# Urukul.net
KiCad netlist of a schematic drawn in Altium Designer
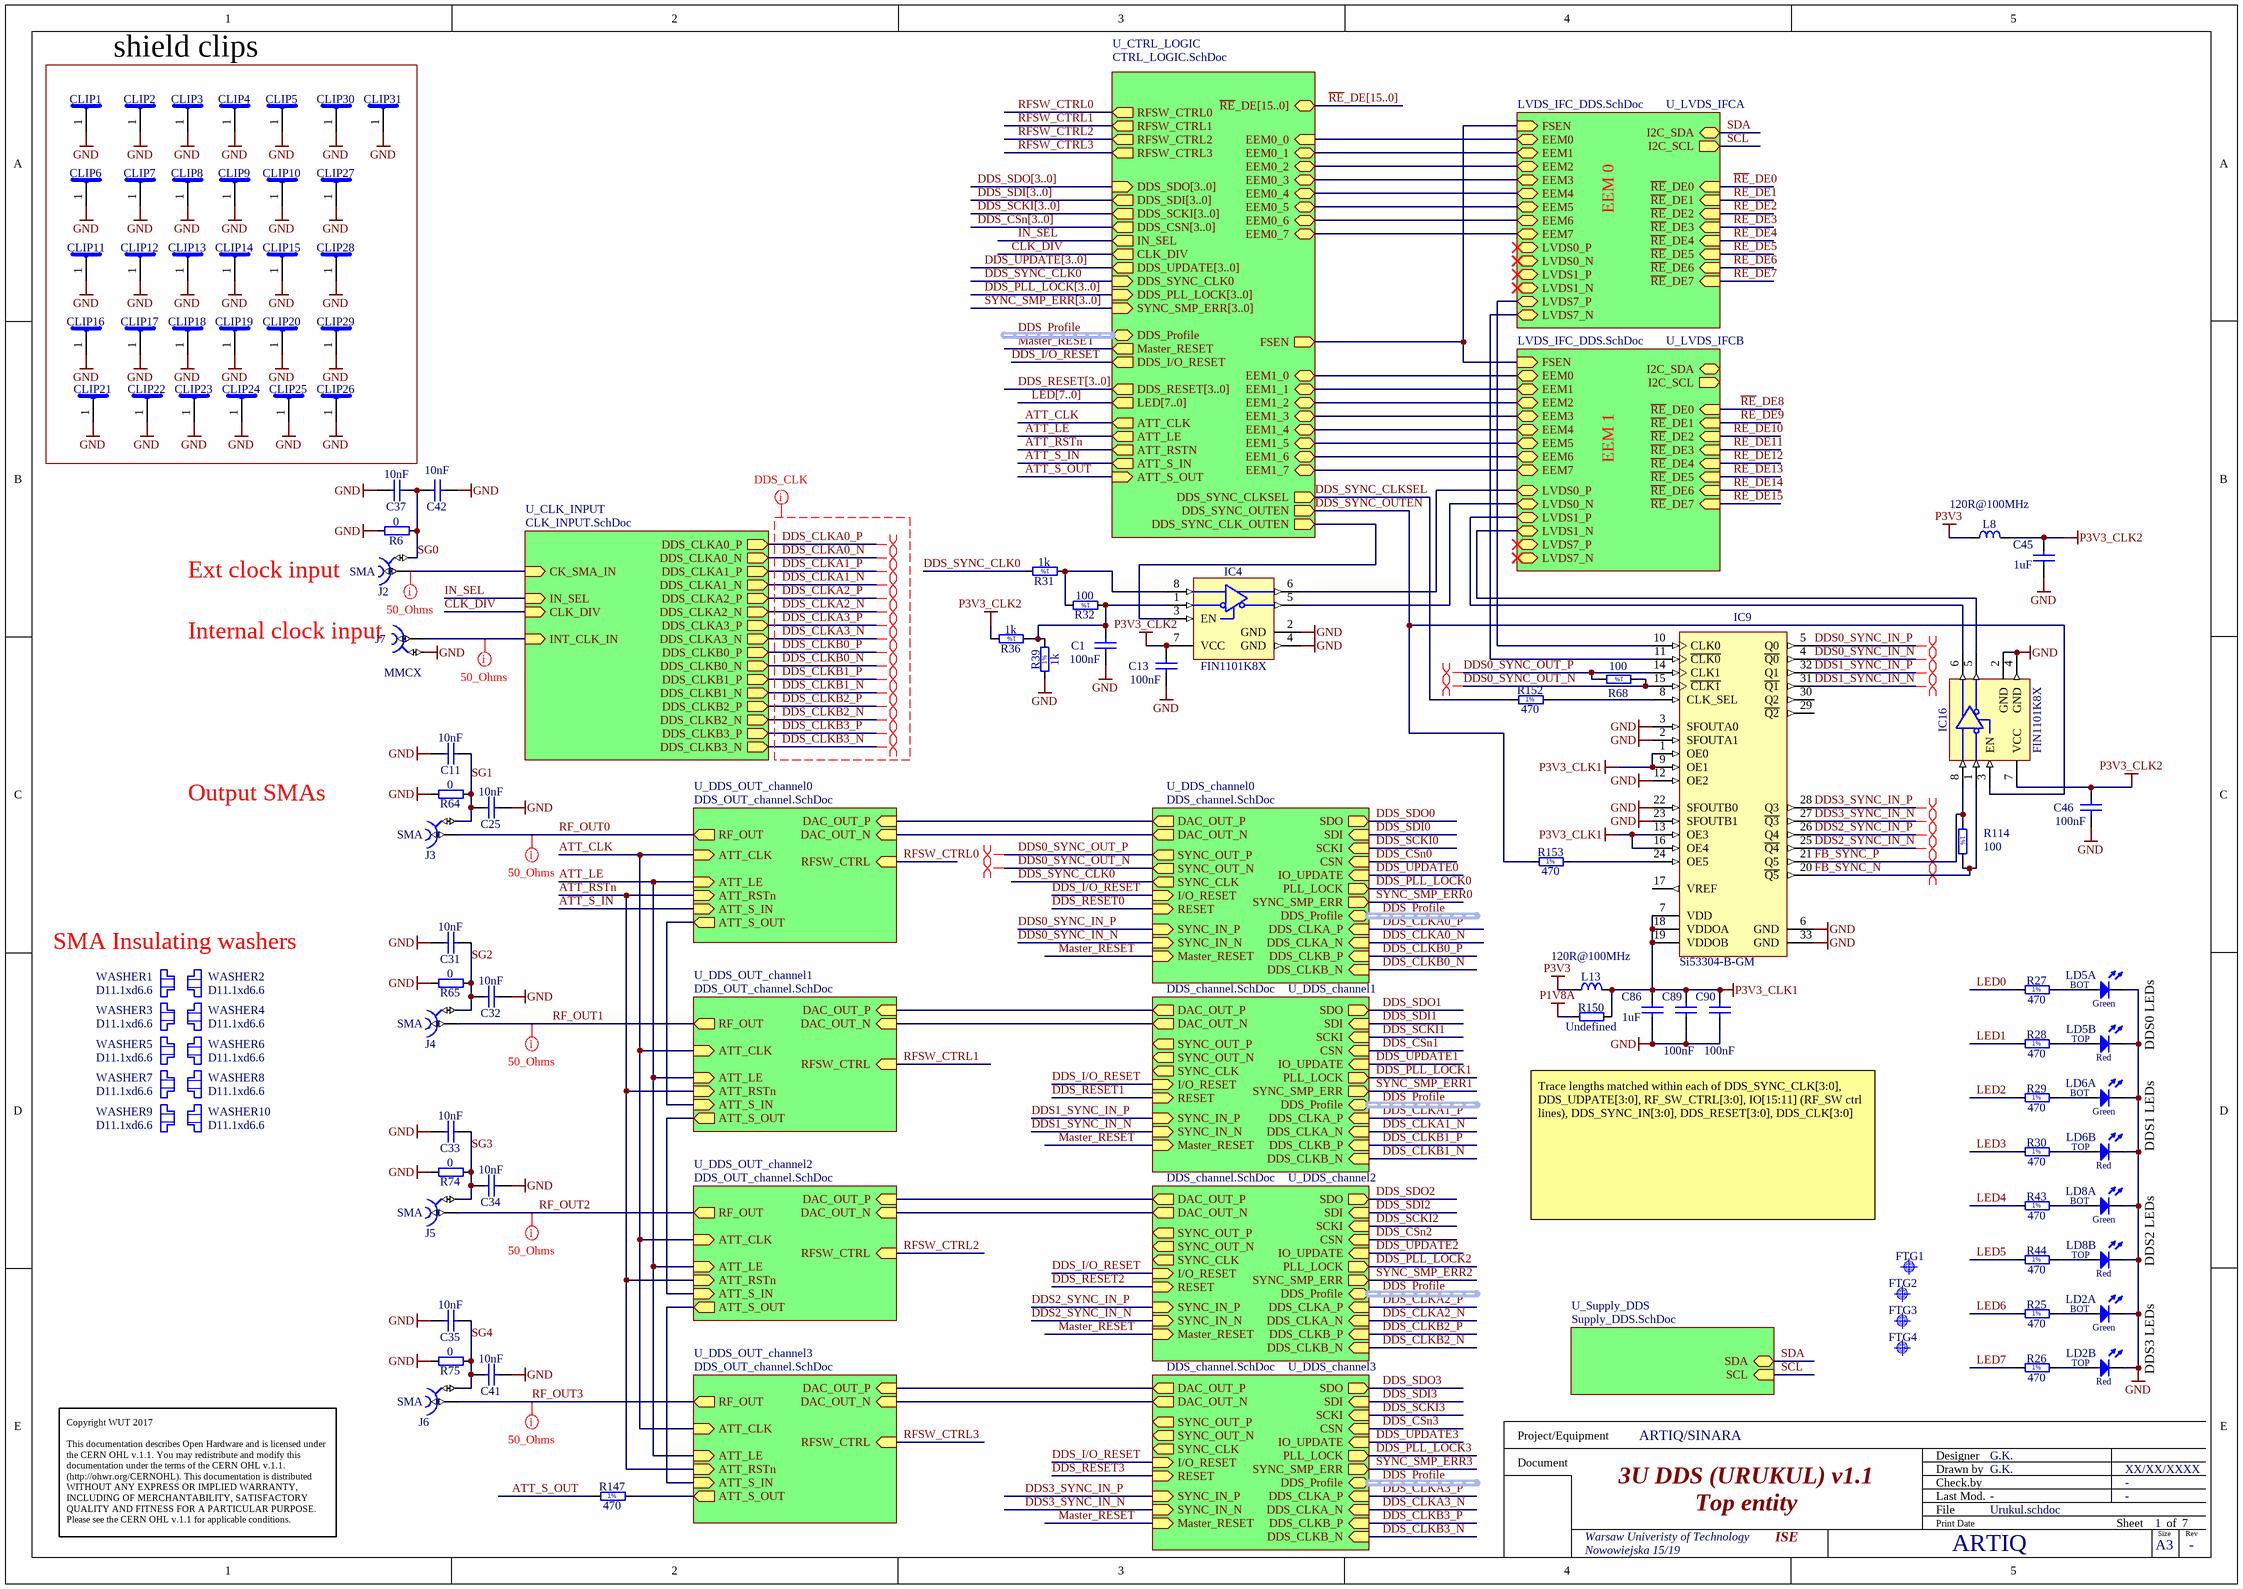
[diagram p0: Urukul.schdoc]

(export (version "E")
  (design (tool "Eeschema 10.0.6"))
  (components
    (comp (ref "C1")
      (value "100nF")
      (footprint "CAPC1005X55N")
      (description "Non-polarised capacitor")
      (fields
        (field (name "PART NUMBER") "CC0402_100NF_16V_10%_X5R")
        (field (name "VOLTAGE") "16V")
        (field (name "AUTHOR") "CERN DEM JLC")
      )
      (libsource (lib "Capacitors") (part "Capacitor - non polarized"))
    )
    (comp (ref "C11")
      (value "10nF")
      (footprint "CAPC1005X55N")
      (description "Non-polarised capacitor")
      (fields
        (field (name "PART NUMBER") "CC0402_10NF_16V_10%_X7R")
        (field (name "VOLTAGE") "16V")
        (field (name "AUTHOR") "CERN DEM JLC")
      )
      (libsource (lib "Capacitors") (part "Capacitor - non polarized"))
    )
    (comp (ref "C13")
      (value "100nF")
      (footprint "CAPC1005X55N")
      (description "Non-polarised capacitor")
      (fields
        (field (name "PART NUMBER") "CC0402_100NF_16V_10%_X5R")
        (field (name "VOLTAGE") "16V")
        (field (name "AUTHOR") "CERN DEM JLC")
      )
      (libsource (lib "Capacitors") (part "Capacitor - non polarized"))
    )
    (comp (ref "C25")
      (value "10nF")
      (footprint "CAPC1005X55N")
      (description "Non-polarised capacitor")
      (fields
        (field (name "PART NUMBER") "CC0402_10NF_16V_10%_X7R")
        (field (name "VOLTAGE") "16V")
        (field (name "AUTHOR") "CERN DEM JLC")
      )
      (libsource (lib "Capacitors") (part "Capacitor - non polarized"))
    )
    (comp (ref "C31")
      (value "10nF")
      (footprint "CAPC1005X55N")
      (description "Non-polarised capacitor")
      (fields
        (field (name "PART NUMBER") "CC0402_10NF_16V_10%_X7R")
        (field (name "VOLTAGE") "16V")
        (field (name "AUTHOR") "CERN DEM JLC")
      )
      (libsource (lib "Capacitors") (part "Capacitor - non polarized"))
    )
    (comp (ref "C32")
      (value "10nF")
      (footprint "CAPC1005X55N")
      (description "Non-polarised capacitor")
      (fields
        (field (name "PART NUMBER") "CC0402_10NF_16V_10%_X7R")
        (field (name "VOLTAGE") "16V")
        (field (name "AUTHOR") "CERN DEM JLC")
      )
      (libsource (lib "Capacitors") (part "Capacitor - non polarized"))
    )
    (comp (ref "C33")
      (value "10nF")
      (footprint "CAPC1005X55N")
      (description "Non-polarised capacitor")
      (fields
        (field (name "PART NUMBER") "CC0402_10NF_16V_10%_X7R")
        (field (name "VOLTAGE") "16V")
        (field (name "AUTHOR") "CERN DEM JLC")
      )
      (libsource (lib "Capacitors") (part "Capacitor - non polarized"))
    )
    (comp (ref "C34")
      (value "10nF")
      (footprint "CAPC1005X55N")
      (description "Non-polarised capacitor")
      (fields
        (field (name "PART NUMBER") "CC0402_10NF_16V_10%_X7R")
        (field (name "VOLTAGE") "16V")
        (field (name "AUTHOR") "CERN DEM JLC")
      )
      (libsource (lib "Capacitors") (part "Capacitor - non polarized"))
    )
    (comp (ref "C35")
      (value "10nF")
      (footprint "CAPC1005X55N")
      (description "Non-polarised capacitor")
      (fields
        (field (name "PART NUMBER") "CC0402_10NF_16V_10%_X7R")
        (field (name "VOLTAGE") "16V")
        (field (name "AUTHOR") "CERN DEM JLC")
      )
      (libsource (lib "Capacitors") (part "Capacitor - non polarized"))
    )
    (comp (ref "C37")
      (value "10nF")
      (footprint "CAPC1005X55N")
      (description "Non-polarised capacitor")
      (fields
        (field (name "PART NUMBER") "CC0402_10NF_16V_10%_X7R")
        (field (name "VOLTAGE") "16V")
        (field (name "AUTHOR") "CERN DEM JLC")
      )
      (libsource (lib "Capacitors") (part "Capacitor - non polarized"))
    )
    (comp (ref "C41")
      (value "10nF")
      (footprint "CAPC1005X55N")
      (description "Non-polarised capacitor")
      (fields
        (field (name "PART NUMBER") "CC0402_10NF_16V_10%_X7R")
        (field (name "VOLTAGE") "16V")
        (field (name "AUTHOR") "CERN DEM JLC")
      )
      (libsource (lib "Capacitors") (part "Capacitor - non polarized"))
    )
    (comp (ref "C42")
      (value "10nF")
      (footprint "CAPC1005X55N")
      (description "Non-polarised capacitor")
      (fields
        (field (name "PART NUMBER") "CC0402_10NF_16V_10%_X7R")
        (field (name "VOLTAGE") "16V")
        (field (name "AUTHOR") "CERN DEM JLC")
      )
      (libsource (lib "Capacitors") (part "Capacitor - non polarized"))
    )
    (comp (ref "C45")
      (value "1uF")
      (footprint "CAPC1005X55N")
      (description "Non-polarised capacitor")
      (fields
        (field (name "PART NUMBER") "CC0402_1UF_16V_10%_X5R")
        (field (name "VOLTAGE") "16V")
        (field (name "AUTHOR") "CERN DEM JLC")
      )
      (libsource (lib "Capacitors") (part "Capacitor - non polarized"))
    )
    (comp (ref "C46")
      (value "100nF")
      (footprint "CAPC1005X55N")
      (description "Non-polarised capacitor")
      (fields
        (field (name "PART NUMBER") "CC0402_100NF_16V_10%_X5R")
        (field (name "VOLTAGE") "16V")
        (field (name "AUTHOR") "CERN DEM JLC")
      )
      (libsource (lib "Capacitors") (part "Capacitor - non polarized"))
    )
    (comp (ref "C86")
      (value "1uF")
      (footprint "CAPC1005X55N")
      (description "Non-polarised capacitor")
      (fields
        (field (name "PART NUMBER") "CC0402_1UF_16V_10%_X5R")
        (field (name "VOLTAGE") "16V")
        (field (name "AUTHOR") "CERN DEM JLC")
      )
      (libsource (lib "Capacitors") (part "Capacitor - non polarized"))
    )
    (comp (ref "C89")
      (value "100nF")
      (footprint "CAPC1005X55N")
      (description "Non-polarised capacitor")
      (fields
        (field (name "PART NUMBER") "CC0402_100NF_16V_10%_X5R")
        (field (name "VOLTAGE") "16V")
        (field (name "AUTHOR") "CERN DEM JLC")
      )
      (libsource (lib "Capacitors") (part "Capacitor - non polarized"))
    )
    (comp (ref "C90")
      (value "100nF")
      (footprint "CAPC1005X55N")
      (description "Non-polarised capacitor")
      (fields
        (field (name "PART NUMBER") "CC0402_100NF_16V_10%_X5R")
        (field (name "VOLTAGE") "16V")
        (field (name "AUTHOR") "CERN DEM JLC")
      )
      (libsource (lib "Capacitors") (part "Capacitor - non polarized"))
    )
    (comp (ref "CLIP1")
      (value "S1411-46R")
      (footprint "CLIP_HOLLAND-SHIELDING_LC")
      (description "Surface Mount Clip for PCB Screening Covers")
      (fields (field (name "MANUFACTURER") "HARWIN") (field (name "AUTHOR") "CERN DEM JLC"))
      (libsource (lib "LIBRARY_SCH") (part "SHIELD_CLIP"))
    )
    (comp (ref "CLIP2")
      (value "S1411-46R")
      (footprint "CLIP_HOLLAND-SHIELDING_LC")
      (description "Surface Mount Clip for PCB Screening Covers")
      (fields (field (name "MANUFACTURER") "HARWIN") (field (name "AUTHOR") "CERN DEM JLC"))
      (libsource (lib "LIBRARY_SCH") (part "SHIELD_CLIP"))
    )
    (comp (ref "CLIP3")
      (value "S1411-46R")
      (footprint "CLIP_HOLLAND-SHIELDING_LC")
      (description "Surface Mount Clip for PCB Screening Covers")
      (fields (field (name "MANUFACTURER") "HARWIN") (field (name "AUTHOR") "CERN DEM JLC"))
      (libsource (lib "LIBRARY_SCH") (part "SHIELD_CLIP"))
    )
    (comp (ref "CLIP4")
      (value "S1411-46R")
      (footprint "CLIP_HOLLAND-SHIELDING_LC")
      (description "Surface Mount Clip for PCB Screening Covers")
      (fields (field (name "MANUFACTURER") "HARWIN") (field (name "AUTHOR") "CERN DEM JLC"))
      (libsource (lib "LIBRARY_SCH") (part "SHIELD_CLIP"))
    )
    (comp (ref "CLIP5")
      (value "S1411-46R")
      (footprint "CLIP_HOLLAND-SHIELDING_LC")
      (description "Surface Mount Clip for PCB Screening Covers")
      (fields (field (name "MANUFACTURER") "HARWIN") (field (name "AUTHOR") "CERN DEM JLC"))
      (libsource (lib "LIBRARY_SCH") (part "SHIELD_CLIP"))
    )
    (comp (ref "CLIP6")
      (value "S1411-46R")
      (footprint "CLIP_HOLLAND-SHIELDING_LC")
      (description "Surface Mount Clip for PCB Screening Covers")
      (fields (field (name "MANUFACTURER") "HARWIN") (field (name "AUTHOR") "CERN DEM JLC"))
      (libsource (lib "LIBRARY_SCH") (part "SHIELD_CLIP"))
    )
    (comp (ref "CLIP7")
      (value "S1411-46R")
      (footprint "CLIP_HOLLAND-SHIELDING_LC")
      (description "Surface Mount Clip for PCB Screening Covers")
      (fields (field (name "MANUFACTURER") "HARWIN") (field (name "AUTHOR") "CERN DEM JLC"))
      (libsource (lib "LIBRARY_SCH") (part "SHIELD_CLIP"))
    )
    (comp (ref "CLIP8")
      (value "S1411-46R")
      (footprint "CLIP_HOLLAND-SHIELDING_LC")
      (description "Surface Mount Clip for PCB Screening Covers")
      (fields (field (name "MANUFACTURER") "HARWIN") (field (name "AUTHOR") "CERN DEM JLC"))
      (libsource (lib "LIBRARY_SCH") (part "SHIELD_CLIP"))
    )
    (comp (ref "CLIP9")
      (value "S1411-46R")
      (footprint "CLIP_HOLLAND-SHIELDING_LC")
      (description "Surface Mount Clip for PCB Screening Covers")
      (fields (field (name "MANUFACTURER") "HARWIN") (field (name "AUTHOR") "CERN DEM JLC"))
      (libsource (lib "LIBRARY_SCH") (part "SHIELD_CLIP"))
    )
    (comp (ref "CLIP10")
      (value "S1411-46R")
      (footprint "CLIP_HOLLAND-SHIELDING_LC")
      (description "Surface Mount Clip for PCB Screening Covers")
      (fields (field (name "MANUFACTURER") "HARWIN") (field (name "AUTHOR") "CERN DEM JLC"))
      (libsource (lib "LIBRARY_SCH") (part "SHIELD_CLIP"))
    )
    (comp (ref "CLIP11")
      (value "S1411-46R")
      (footprint "CLIP_HOLLAND-SHIELDING_LC")
      (description "Surface Mount Clip for PCB Screening Covers")
      (fields (field (name "MANUFACTURER") "HARWIN") (field (name "AUTHOR") "CERN DEM JLC"))
      (libsource (lib "LIBRARY_SCH") (part "SHIELD_CLIP"))
    )
    (comp (ref "CLIP12")
      (value "S1411-46R")
      (footprint "CLIP_HOLLAND-SHIELDING_LC")
      (description "Surface Mount Clip for PCB Screening Covers")
      (fields (field (name "MANUFACTURER") "HARWIN") (field (name "AUTHOR") "CERN DEM JLC"))
      (libsource (lib "LIBRARY_SCH") (part "SHIELD_CLIP"))
    )
    (comp (ref "CLIP13")
      (value "S1411-46R")
      (footprint "CLIP_HOLLAND-SHIELDING_LC")
      (description "Surface Mount Clip for PCB Screening Covers")
      (fields (field (name "MANUFACTURER") "HARWIN") (field (name "AUTHOR") "CERN DEM JLC"))
      (libsource (lib "LIBRARY_SCH") (part "SHIELD_CLIP"))
    )
    (comp (ref "CLIP14")
      (value "S1411-46R")
      (footprint "CLIP_HOLLAND-SHIELDING_LC")
      (description "Surface Mount Clip for PCB Screening Covers")
      (fields (field (name "MANUFACTURER") "HARWIN") (field (name "AUTHOR") "CERN DEM JLC"))
      (libsource (lib "LIBRARY_SCH") (part "SHIELD_CLIP"))
    )
    (comp (ref "CLIP15")
      (value "S1411-46R")
      (footprint "CLIP_HOLLAND-SHIELDING_LC")
      (description "Surface Mount Clip for PCB Screening Covers")
      (fields (field (name "MANUFACTURER") "HARWIN") (field (name "AUTHOR") "CERN DEM JLC"))
      (libsource (lib "LIBRARY_SCH") (part "SHIELD_CLIP"))
    )
    (comp (ref "CLIP16")
      (value "S1411-46R")
      (footprint "CLIP_HOLLAND-SHIELDING_LC")
      (description "Surface Mount Clip for PCB Screening Covers")
      (fields (field (name "MANUFACTURER") "HARWIN") (field (name "AUTHOR") "CERN DEM JLC"))
      (libsource (lib "LIBRARY_SCH") (part "SHIELD_CLIP"))
    )
    (comp (ref "CLIP17")
      (value "S1411-46R")
      (footprint "CLIP_HOLLAND-SHIELDING_LC")
      (description "Surface Mount Clip for PCB Screening Covers")
      (fields (field (name "MANUFACTURER") "HARWIN") (field (name "AUTHOR") "CERN DEM JLC"))
      (libsource (lib "LIBRARY_SCH") (part "SHIELD_CLIP"))
    )
    (comp (ref "CLIP18")
      (value "S1411-46R")
      (footprint "CLIP_HOLLAND-SHIELDING_LC")
      (description "Surface Mount Clip for PCB Screening Covers")
      (fields (field (name "MANUFACTURER") "HARWIN") (field (name "AUTHOR") "CERN DEM JLC"))
      (libsource (lib "LIBRARY_SCH") (part "SHIELD_CLIP"))
    )
    (comp (ref "CLIP19")
      (value "S1411-46R")
      (footprint "CLIP_HOLLAND-SHIELDING_LC")
      (description "Surface Mount Clip for PCB Screening Covers")
      (fields (field (name "MANUFACTURER") "HARWIN") (field (name "AUTHOR") "CERN DEM JLC"))
      (libsource (lib "LIBRARY_SCH") (part "SHIELD_CLIP"))
    )
    (comp (ref "CLIP20")
      (value "S1411-46R")
      (footprint "CLIP_HOLLAND-SHIELDING_LC")
      (description "Surface Mount Clip for PCB Screening Covers")
      (fields (field (name "MANUFACTURER") "HARWIN") (field (name "AUTHOR") "CERN DEM JLC"))
      (libsource (lib "LIBRARY_SCH") (part "SHIELD_CLIP"))
    )
    (comp (ref "CLIP21")
      (value "S1411-46R")
      (footprint "CLIP_HOLLAND-SHIELDING_LC")
      (description "Surface Mount Clip for PCB Screening Covers")
      (fields (field (name "MANUFACTURER") "HARWIN") (field (name "AUTHOR") "CERN DEM JLC"))
      (libsource (lib "LIBRARY_SCH") (part "SHIELD_CLIP"))
    )
    (comp (ref "CLIP22")
      (value "S1411-46R")
      (footprint "CLIP_HOLLAND-SHIELDING_LC")
      (description "Surface Mount Clip for PCB Screening Covers")
      (fields (field (name "MANUFACTURER") "HARWIN") (field (name "AUTHOR") "CERN DEM JLC"))
      (libsource (lib "LIBRARY_SCH") (part "SHIELD_CLIP"))
    )
    (comp (ref "CLIP23")
      (value "S1411-46R")
      (footprint "CLIP_HOLLAND-SHIELDING_LC")
      (description "Surface Mount Clip for PCB Screening Covers")
      (fields (field (name "MANUFACTURER") "HARWIN") (field (name "AUTHOR") "CERN DEM JLC"))
      (libsource (lib "LIBRARY_SCH") (part "SHIELD_CLIP"))
    )
    (comp (ref "CLIP24")
      (value "S1411-46R")
      (footprint "CLIP_HOLLAND-SHIELDING_LC")
      (description "Surface Mount Clip for PCB Screening Covers")
      (fields (field (name "MANUFACTURER") "HARWIN") (field (name "AUTHOR") "CERN DEM JLC"))
      (libsource (lib "LIBRARY_SCH") (part "SHIELD_CLIP"))
    )
    (comp (ref "CLIP25")
      (value "S1411-46R")
      (footprint "CLIP_HOLLAND-SHIELDING_LC")
      (description "Surface Mount Clip for PCB Screening Covers")
      (fields (field (name "MANUFACTURER") "HARWIN") (field (name "AUTHOR") "CERN DEM JLC"))
      (libsource (lib "LIBRARY_SCH") (part "SHIELD_CLIP"))
    )
    (comp (ref "CLIP26")
      (value "S1411-46R")
      (footprint "CLIP_HOLLAND-SHIELDING_LC")
      (description "Surface Mount Clip for PCB Screening Covers")
      (fields (field (name "MANUFACTURER") "HARWIN") (field (name "AUTHOR") "CERN DEM JLC"))
      (libsource (lib "LIBRARY_SCH") (part "SHIELD_CLIP"))
    )
    (comp (ref "CLIP27")
      (value "S1411-46R")
      (footprint "CLIP_HOLLAND-SHIELDING_LC")
      (description "Surface Mount Clip for PCB Screening Covers")
      (fields (field (name "MANUFACTURER") "HARWIN") (field (name "AUTHOR") "CERN DEM JLC"))
      (libsource (lib "LIBRARY_SCH") (part "SHIELD_CLIP"))
    )
    (comp (ref "CLIP28")
      (value "S1411-46R")
      (footprint "CLIP_HOLLAND-SHIELDING_LC")
      (description "Surface Mount Clip for PCB Screening Covers")
      (fields (field (name "MANUFACTURER") "HARWIN") (field (name "AUTHOR") "CERN DEM JLC"))
      (libsource (lib "LIBRARY_SCH") (part "SHIELD_CLIP"))
    )
    (comp (ref "CLIP29")
      (value "S1411-46R")
      (footprint "CLIP_HOLLAND-SHIELDING_LC")
      (description "Surface Mount Clip for PCB Screening Covers")
      (fields (field (name "MANUFACTURER") "HARWIN") (field (name "AUTHOR") "CERN DEM JLC"))
      (libsource (lib "LIBRARY_SCH") (part "SHIELD_CLIP"))
    )
    (comp (ref "CLIP30")
      (value "S1411-46R")
      (footprint "CLIP_HOLLAND-SHIELDING_LC")
      (description "Surface Mount Clip for PCB Screening Covers")
      (fields (field (name "MANUFACTURER") "HARWIN") (field (name "AUTHOR") "CERN DEM JLC"))
      (libsource (lib "LIBRARY_SCH") (part "SHIELD_CLIP"))
    )
    (comp (ref "CLIP31")
      (value "S1411-46R")
      (footprint "CLIP_HOLLAND-SHIELDING_LC")
      (description "Surface Mount Clip for PCB Screening Covers")
      (fields (field (name "MANUFACTURER") "HARWIN") (field (name "AUTHOR") "CERN DEM JLC"))
      (libsource (lib "LIBRARY_SCH") (part "SHIELD_CLIP"))
    )
    (comp (ref "FTG1")
      (value "Use only in PCB")
      (footprint "FIDUCIAL_TOP_C100-200")
      (description "Fiducial Target")
      (fields (field (name "PART NUMBER") "FIDUCIAL_TARGET_C100-200") (field (name "AUTHOR") "CERN DEM JLC"))
      (libsource (lib "Eletro-mechanical") (part "Fiducial Target"))
    )
    (comp (ref "FTG2")
      (value "Use only in PCB")
      (footprint "FIDUCIAL_TOP_S100-200")
      (description "Fiducial Target")
      (fields (field (name "PART NUMBER") "FIDUCIAL_TARGET_S100-200") (field (name "AUTHOR") "CERN DEM JLC"))
      (libsource (lib "Eletro-mechanical") (part "Fiducial Target"))
    )
    (comp (ref "FTG3")
      (value "Use only in PCB")
      (footprint "FIDUCIAL_TOP_S200-400")
      (description "Fiducial Target")
      (fields (field (name "PART NUMBER") "FIDUCIAL_TARGET_S200-400") (field (name "AUTHOR") "CERN DEM JLC"))
      (libsource (lib "Eletro-mechanical") (part "Fiducial Target"))
    )
    (comp (ref "FTG4")
      (value "Use only in PCB")
      (footprint "FIDUCIAL_TOP_S100-200")
      (description "Fiducial Target")
      (fields (field (name "PART NUMBER") "FIDUCIAL_TARGET_S100-200") (field (name "AUTHOR") "CERN DEM JLC"))
      (libsource (lib "Eletro-mechanical") (part "Fiducial Target"))
    )
    (comp (ref "IC4")
      (value "FIN1101K8X")
      (footprint "SOP50P310X90-8N")
      (description "LVDS Single Port High Speed Repeater")
      (fields (field (name "MANUFACTURER") "FAIRCHILD SEMICONDUCTOR") (field (name "AUTHOR") "CERN DEM JLC"))
      (libsource (lib "") (part "FIN1101K8X_1"))
    )
    (comp (ref "IC9")
      (value "Si53304-B-GM")
      (footprint "SLAB-QFN-32-2150x2150TP_M")
      (fields (field (name "MANUFACTURER") "Silicon Labs"))
      (libsource (lib "Altium Content Vault") (part "SLAB-Si533X4-QFN-32-33"))
    )
    (comp (ref "IC16")
      (value "FIN1101K8X")
      (footprint "SOP50P310X90-8N")
      (description "LVDS Single Port High Speed Repeater")
      (fields (field (name "MANUFACTURER") "FAIRCHILD SEMICONDUCTOR") (field (name "AUTHOR") "CERN DEM JLC"))
      (libsource (lib "ICs And Semiconductors") (part "FIN1101K8X"))
    )
    (comp (ref "J2")
      (value "SMA")
      (footprint "RF249BT0050GHDW")
      (description "50 Ohm Through Hole SMA Right Angle PCB Jack")
      (fields
        (field (name "PART NUMBER") "AdamTech_RF249BT0050GHDW")
        (field (name "MANUFACTURER") "AdamTech")
        (field (name "AUTHOR") "GK")
      )
      (libsource (lib "LIBRARY_SCH") (part "CON_SMA_RF249BT0050GHDW"))
    )
    (comp (ref "J3")
      (value "SMA")
      (footprint "RF249BT0050GHDW")
      (description "50 Ohm Through Hole SMA Right Angle PCB Jack")
      (fields
        (field (name "PART NUMBER") "AdamTech_RF249BT0050GHDW")
        (field (name "MANUFACTURER") "AdamTech")
        (field (name "AUTHOR") "GK")
      )
      (libsource (lib "LIBRARY_SCH") (part "CON_SMA_RF249BT0050GHDW"))
    )
    (comp (ref "J4")
      (value "SMA")
      (footprint "RF249BT0050GHDW")
      (description "50 Ohm Through Hole SMA Right Angle PCB Jack")
      (fields
        (field (name "PART NUMBER") "AdamTech_RF249BT0050GHDW")
        (field (name "MANUFACTURER") "AdamTech")
        (field (name "AUTHOR") "GK")
      )
      (libsource (lib "LIBRARY_SCH") (part "CON_SMA_RF249BT0050GHDW"))
    )
    (comp (ref "J5")
      (value "SMA")
      (footprint "RF249BT0050GHDW")
      (description "50 Ohm Through Hole SMA Right Angle PCB Jack")
      (fields
        (field (name "PART NUMBER") "AdamTech_RF249BT0050GHDW")
        (field (name "MANUFACTURER") "AdamTech")
        (field (name "AUTHOR") "GK")
      )
      (libsource (lib "LIBRARY_SCH") (part "CON_SMA_RF249BT0050GHDW"))
    )
    (comp (ref "J6")
      (value "SMA")
      (footprint "RF249BT0050GHDW")
      (description "50 Ohm Through Hole SMA Right Angle PCB Jack")
      (fields
        (field (name "PART NUMBER") "AdamTech_RF249BT0050GHDW")
        (field (name "MANUFACTURER") "AdamTech")
        (field (name "AUTHOR") "GK")
      )
      (libsource (lib "LIBRARY_SCH") (part "CON_SMA_RF249BT0050GHDW"))
    )
    (comp (ref "J7")
      (value "MMCX")
      (footprint "SAMTEC_MMCX-J-P-H-ST-TH1")
      (fields
        (field (name "PART NUMBER") "SAMTEC_MMCX-J-P-H-ST-TH1")
        (field (name "MANUFACTURER") "SAMTEC")
        (field (name "MANUFACTURER PART NUMBER") "MMCX-J-P-H-ST-TH1")
        (field (name "AUTHOR") "CERN DEM JLC")
      )
      (libsource (lib "Connectors") (part "Coax_1Female_1Shield"))
    )
    (comp (ref "L8")
      (value "120R@100MHz")
      (footprint "INDC1608X95N")
      (description "Inductor")
      (fields
        (field (name "PART NUMBER") "IND0603_MURATA_BLM18PG121SN1D")
        (field (name "POWER") "2A")
        (field (name "AUTHOR") "CERN DEM BC")
      )
      (libsource (lib "Inductors & Transformers") (part "Inductor"))
    )
    (comp (ref "L13")
      (value "120R@100MHz")
      (footprint "INDC1608X95N")
      (description "Inductor")
      (fields
        (field (name "PART NUMBER") "IND0603_MURATA_BLM18PG121SN1D")
        (field (name "POWER") "2A")
        (field (name "AUTHOR") "CERN DEM BC")
      )
      (libsource (lib "Inductors & Transformers") (part "Inductor"))
    )
    (comp (ref "LD2")
      (value "Red/Green")
      (footprint "LED_DIALIGHT_553-0112-200F")
      (description "2x LED  Botom Green, Top Red")
      (fields
        (field (name "PART NUMBER") "LED_DIALIGHT_553-0112-200F")
        (field (name "MANUFACTURER") "DIALIGHT")
        (field (name "AUTHOR") "CERN DEM JMW")
      )
      (libsource (lib "ICs And Semiconductors") (part "LED x2 G-1C2A-BOT_R-3C4A-TOP"))
    )
    (comp (ref "LD5")
      (value "Red/Green")
      (footprint "LED_DIALIGHT_553-0112-200F")
      (description "2x LED  Botom Green, Top Red")
      (fields
        (field (name "PART NUMBER") "LED_DIALIGHT_553-0112-200F")
        (field (name "MANUFACTURER") "DIALIGHT")
        (field (name "AUTHOR") "CERN DEM JMW")
      )
      (libsource (lib "ICs And Semiconductors") (part "LED x2 G-1C2A-BOT_R-3C4A-TOP"))
    )
    (comp (ref "LD6")
      (value "Red/Green")
      (footprint "LED_DIALIGHT_553-0112-200F")
      (description "2x LED  Botom Green, Top Red")
      (fields
        (field (name "PART NUMBER") "LED_DIALIGHT_553-0112-200F")
        (field (name "MANUFACTURER") "DIALIGHT")
        (field (name "AUTHOR") "CERN DEM JMW")
      )
      (libsource (lib "ICs And Semiconductors") (part "LED x2 G-1C2A-BOT_R-3C4A-TOP"))
    )
    (comp (ref "LD8")
      (value "Red/Green")
      (footprint "LED_DIALIGHT_553-0112-200F")
      (description "2x LED  Botom Green, Top Red")
      (fields
        (field (name "PART NUMBER") "LED_DIALIGHT_553-0112-200F")
        (field (name "MANUFACTURER") "DIALIGHT")
        (field (name "AUTHOR") "CERN DEM JMW")
      )
      (libsource (lib "ICs And Semiconductors") (part "LED x2 G-1C2A-BOT_R-3C4A-TOP"))
    )
    (comp (ref "R6")
      (value "0")
      (footprint "RESC1005X40N")
      (description "Resistor")
      (fields
        (field (name "PART NUMBER") "R0402_0R_JUMPER")
        (field (name "MANUFACTURER") "GENERIC")
        (field (name "AUTHOR") "CERN DEM JLC")
      )
      (libsource (lib "Resistors") (part "Resistor"))
    )
    (comp (ref "R25")
      (value "470")
      (footprint "RESC1005X40N")
      (description "Resistor - 1%")
      (fields
        (field (name "PART NUMBER") "R0402_470R_1%_0.0625W_100PPM")
        (field (name "POWER") "0.0625W")
        (field (name "AUTHOR") "CERN DEM JLC")
      )
      (libsource (lib "Resistors") (part "Resistor - 1%"))
    )
    (comp (ref "R26")
      (value "470")
      (footprint "RESC1005X40N")
      (description "Resistor - 1%")
      (fields
        (field (name "PART NUMBER") "R0402_470R_1%_0.0625W_100PPM")
        (field (name "POWER") "0.0625W")
        (field (name "AUTHOR") "CERN DEM JLC")
      )
      (libsource (lib "Resistors") (part "Resistor - 1%"))
    )
    (comp (ref "R27")
      (value "470")
      (footprint "RESC1005X40N")
      (description "Resistor - 1%")
      (fields
        (field (name "PART NUMBER") "R0402_470R_1%_0.0625W_100PPM")
        (field (name "POWER") "0.0625W")
        (field (name "AUTHOR") "CERN DEM JLC")
      )
      (libsource (lib "Resistors") (part "Resistor - 1%"))
    )
    (comp (ref "R28")
      (value "470")
      (footprint "RESC1005X40N")
      (description "Resistor - 1%")
      (fields
        (field (name "PART NUMBER") "R0402_470R_1%_0.0625W_100PPM")
        (field (name "POWER") "0.0625W")
        (field (name "AUTHOR") "CERN DEM JLC")
      )
      (libsource (lib "Resistors") (part "Resistor - 1%"))
    )
    (comp (ref "R29")
      (value "470")
      (footprint "RESC1005X40N")
      (description "Resistor - 1%")
      (fields
        (field (name "PART NUMBER") "R0402_470R_1%_0.0625W_100PPM")
        (field (name "POWER") "0.0625W")
        (field (name "AUTHOR") "CERN DEM JLC")
      )
      (libsource (lib "Resistors") (part "Resistor - 1%"))
    )
    (comp (ref "R30")
      (value "470")
      (footprint "RESC1005X40N")
      (description "Resistor - 1%")
      (fields
        (field (name "PART NUMBER") "R0402_470R_1%_0.0625W_100PPM")
        (field (name "POWER") "0.0625W")
        (field (name "AUTHOR") "CERN DEM JLC")
      )
      (libsource (lib "Resistors") (part "Resistor - 1%"))
    )
    (comp (ref "R31")
      (value "1k")
      (footprint "RESC1005X40N")
      (description "Resistor - 1%")
      (fields
        (field (name "PART NUMBER") "R0402_1K_1%_0.0625W_100PPM")
        (field (name "POWER") "0.0625W")
        (field (name "AUTHOR") "CERN DEM JLC")
      )
      (libsource (lib "Resistors") (part "Resistor - 1%"))
    )
    (comp (ref "R32")
      (value "100")
      (footprint "RESC1005X40N")
      (description "Resistor - 1%")
      (fields
        (field (name "PART NUMBER") "R0402_100R_1%_0.0625W_100PPM")
        (field (name "POWER") "0.0625W")
        (field (name "AUTHOR") "CERN DEM JLC")
      )
      (libsource (lib "Resistors") (part "Resistor - 1%"))
    )
    (comp (ref "R36")
      (value "1k")
      (footprint "RESC1005X40N")
      (description "Resistor - 1%")
      (fields
        (field (name "PART NUMBER") "R0402_1K_1%_0.0625W_100PPM")
        (field (name "POWER") "0.0625W")
        (field (name "AUTHOR") "CERN DEM JLC")
      )
      (libsource (lib "Resistors") (part "Resistor - 1%"))
    )
    (comp (ref "R39")
      (value "1k")
      (footprint "RESC1005X40N")
      (description "Resistor - 1%")
      (fields
        (field (name "PART NUMBER") "R0402_1K_1%_0.0625W_100PPM")
        (field (name "POWER") "0.0625W")
        (field (name "AUTHOR") "CERN DEM JLC")
      )
      (libsource (lib "Resistors") (part "Resistor - 1%"))
    )
    (comp (ref "R43")
      (value "470")
      (footprint "RESC1005X40N")
      (description "Resistor - 1%")
      (fields
        (field (name "PART NUMBER") "R0402_470R_1%_0.0625W_100PPM")
        (field (name "POWER") "0.0625W")
        (field (name "AUTHOR") "CERN DEM JLC")
      )
      (libsource (lib "Resistors") (part "Resistor - 1%"))
    )
    (comp (ref "R44")
      (value "470")
      (footprint "RESC1005X40N")
      (description "Resistor - 1%")
      (fields
        (field (name "PART NUMBER") "R0402_470R_1%_0.0625W_100PPM")
        (field (name "POWER") "0.0625W")
        (field (name "AUTHOR") "CERN DEM JLC")
      )
      (libsource (lib "Resistors") (part "Resistor - 1%"))
    )
    (comp (ref "R64")
      (value "0")
      (footprint "RESC1005X40N")
      (description "Resistor")
      (fields
        (field (name "PART NUMBER") "R0402_0R_JUMPER")
        (field (name "MANUFACTURER") "GENERIC")
        (field (name "AUTHOR") "CERN DEM JLC")
      )
      (libsource (lib "Resistors") (part "Resistor"))
    )
    (comp (ref "R65")
      (value "0")
      (footprint "RESC1005X40N")
      (description "Resistor")
      (fields
        (field (name "PART NUMBER") "R0402_0R_JUMPER")
        (field (name "MANUFACTURER") "GENERIC")
        (field (name "AUTHOR") "CERN DEM JLC")
      )
      (libsource (lib "Resistors") (part "Resistor"))
    )
    (comp (ref "R68")
      (value "100")
      (footprint "RESC1005X40N")
      (description "Resistor - 1%")
      (fields
        (field (name "PART NUMBER") "R0402_100R_1%_0.0625W_100PPM")
        (field (name "POWER") "0.0625W")
        (field (name "AUTHOR") "CERN DEM JLC")
      )
      (libsource (lib "Resistors") (part "Resistor - 1%"))
    )
    (comp (ref "R74")
      (value "0")
      (footprint "RESC1005X40N")
      (description "Resistor")
      (fields
        (field (name "PART NUMBER") "R0402_0R_JUMPER")
        (field (name "MANUFACTURER") "GENERIC")
        (field (name "AUTHOR") "CERN DEM JLC")
      )
      (libsource (lib "Resistors") (part "Resistor"))
    )
    (comp (ref "R75")
      (value "0")
      (footprint "RESC1005X40N")
      (description "Resistor")
      (fields
        (field (name "PART NUMBER") "R0402_0R_JUMPER")
        (field (name "MANUFACTURER") "GENERIC")
        (field (name "AUTHOR") "CERN DEM JLC")
      )
      (libsource (lib "Resistors") (part "Resistor"))
    )
    (comp (ref "R114")
      (value "100")
      (footprint "RESC1005X40N")
      (description "Resistor - 1%")
      (fields
        (field (name "PART NUMBER") "R0402_100R_1%_0.0625W_100PPM")
        (field (name "POWER") "0.0625W")
        (field (name "AUTHOR") "CERN DEM JLC")
      )
      (libsource (lib "Resistors") (part "Resistor - 1%"))
    )
    (comp (ref "R147")
      (value "470")
      (footprint "RESC1005X40N")
      (description "Resistor - 1%")
      (fields
        (field (name "PART NUMBER") "R0402_470R_1%_0.0625W_100PPM")
        (field (name "POWER") "0.0625W")
        (field (name "AUTHOR") "CERN DEM JLC")
      )
      (libsource (lib "Resistors") (part "Resistor - 1%"))
    )
    (comp (ref "R150")
      (value "Undefined")
      (footprint "RESC1608X55N")
      (description "Resistor")
      (fields (field (name "PART NUMBER") "R0603_NO-VALUE") (field (name "AUTHOR") "CERN DEM JLC"))
      (libsource (lib "Resistors") (part "Resistor"))
    )
    (comp (ref "R152")
      (value "470")
      (footprint "RESC1005X40N")
      (description "Resistor - 1%")
      (fields
        (field (name "PART NUMBER") "R0402_470R_1%_0.0625W_100PPM")
        (field (name "POWER") "0.0625W")
        (field (name "AUTHOR") "CERN DEM JLC")
      )
      (libsource (lib "Resistors") (part "Resistor - 1%"))
    )
    (comp (ref "R153")
      (value "470")
      (footprint "RESC1005X40N")
      (description "Resistor - 1%")
      (fields
        (field (name "PART NUMBER") "R0402_470R_1%_0.0625W_100PPM")
        (field (name "POWER") "0.0625W")
        (field (name "AUTHOR") "CERN DEM JLC")
      )
      (libsource (lib "Resistors") (part "Resistor - 1%"))
    )
    (comp (ref "WASHER1")
      (value "D11.1xd6.6")
      (footprint "Keystone_7687")
      (description "SMA_Shoulder Washer")
      (fields
        (field (name "PART NUMBER") "Keystone 7687")
        (field (name "MANUFACTURER") "Keystone")
        (field (name "AUTHOR") "GK")
      )
      (libsource (lib "LIBRARY_SCH") (part "Keystone_7687"))
    )
    (comp (ref "WASHER2")
      (value "D11.1xd6.6")
      (footprint "Keystone_7687")
      (description "SMA_Shoulder Washer")
      (fields
        (field (name "PART NUMBER") "Keystone 7687")
        (field (name "MANUFACTURER") "Keystone")
        (field (name "AUTHOR") "GK")
      )
      (libsource (lib "LIBRARY_SCH") (part "Keystone_7687"))
    )
    (comp (ref "WASHER3")
      (value "D11.1xd6.6")
      (footprint "Keystone_7687")
      (description "SMA_Shoulder Washer")
      (fields
        (field (name "PART NUMBER") "Keystone 7687")
        (field (name "MANUFACTURER") "Keystone")
        (field (name "AUTHOR") "GK")
      )
      (libsource (lib "LIBRARY_SCH") (part "Keystone_7687"))
    )
    (comp (ref "WASHER4")
      (value "D11.1xd6.6")
      (footprint "Keystone_7687")
      (description "SMA_Shoulder Washer")
      (fields
        (field (name "PART NUMBER") "Keystone 7687")
        (field (name "MANUFACTURER") "Keystone")
        (field (name "AUTHOR") "GK")
      )
      (libsource (lib "LIBRARY_SCH") (part "Keystone_7687"))
    )
    (comp (ref "WASHER5")
      (value "D11.1xd6.6")
      (footprint "Keystone_7687")
      (description "SMA_Shoulder Washer")
      (fields
        (field (name "PART NUMBER") "Keystone 7687")
        (field (name "MANUFACTURER") "Keystone")
        (field (name "AUTHOR") "GK")
      )
      (libsource (lib "LIBRARY_SCH") (part "Keystone_7687"))
    )
    (comp (ref "WASHER6")
      (value "D11.1xd6.6")
      (footprint "Keystone_7687")
      (description "SMA_Shoulder Washer")
      (fields
        (field (name "PART NUMBER") "Keystone 7687")
        (field (name "MANUFACTURER") "Keystone")
        (field (name "AUTHOR") "GK")
      )
      (libsource (lib "LIBRARY_SCH") (part "Keystone_7687"))
    )
    (comp (ref "WASHER7")
      (value "D11.1xd6.6")
      (footprint "Keystone_7687")
      (description "SMA_Shoulder Washer")
      (fields
        (field (name "PART NUMBER") "Keystone 7687")
        (field (name "MANUFACTURER") "Keystone")
        (field (name "AUTHOR") "GK")
      )
      (libsource (lib "LIBRARY_SCH") (part "Keystone_7687"))
    )
    (comp (ref "WASHER8")
      (value "D11.1xd6.6")
      (footprint "Keystone_7687")
      (description "SMA_Shoulder Washer")
      (fields
        (field (name "PART NUMBER") "Keystone 7687")
        (field (name "MANUFACTURER") "Keystone")
        (field (name "AUTHOR") "GK")
      )
      (libsource (lib "LIBRARY_SCH") (part "Keystone_7687"))
    )
    (comp (ref "WASHER9")
      (value "D11.1xd6.6")
      (footprint "Keystone_7687")
      (description "SMA_Shoulder Washer")
      (fields
        (field (name "PART NUMBER") "Keystone 7687")
        (field (name "MANUFACTURER") "Keystone")
        (field (name "AUTHOR") "GK")
      )
      (libsource (lib "LIBRARY_SCH") (part "Keystone_7687"))
    )
    (comp (ref "WASHER10")
      (value "D11.1xd6.6")
      (footprint "Keystone_7687")
      (description "SMA_Shoulder Washer")
      (fields
        (field (name "PART NUMBER") "Keystone 7687")
        (field (name "MANUFACTURER") "Keystone")
        (field (name "AUTHOR") "GK")
      )
      (libsource (lib "LIBRARY_SCH") (part "Keystone_7687"))
    )
  )
  (nets
    (net (code "6") (name "/ATT_S_OUT") (class "Default")
      (node (ref "R147") (pin "1") (pinfunction "1_1") (pintype "passive"))
    )
    (net (code "7") (name "/ATT_S_OUT_1") (class "Default")
      (node (ref "R147") (pin "2") (pinfunction "2_2") (pintype "passive"))
    )
    (net (code "11") (name "/CK_SMA_IN") (class "Default")
      (node (ref "J2") (pin "1") (pinfunction "1_1") (pintype "bidirectional"))
    )
    (net (code "21") (name "/DDS0_SYNC_IN_N") (class "Default")
      (node (ref "IC9") (pin "4") (pinfunction "~{Q0}_4") (pintype "output"))
    )
    (net (code "22") (name "/DDS0_SYNC_IN_P") (class "Default")
      (node (ref "IC9") (pin "5") (pinfunction "Q0_5") (pintype "output"))
    )
    (net (code "23") (name "/DDS0_SYNC_OUT_N") (class "Default")
      (node (ref "IC9") (pin "15") (pinfunction "~{CLK1}_15") (pintype "input"))
      (node (ref "R68") (pin "1") (pinfunction "1_1") (pintype "passive"))
    )
    (net (code "24") (name "/DDS0_SYNC_OUT_P") (class "Default")
      (node (ref "IC9") (pin "14") (pinfunction "CLK1_14") (pintype "input"))
      (node (ref "R68") (pin "2") (pinfunction "2_2") (pintype "passive"))
    )
    (net (code "25") (name "/DDS1_SYNC_IN_N") (class "Default")
      (node (ref "IC9") (pin "31") (pinfunction "~{Q1}_31") (pintype "output"))
    )
    (net (code "26") (name "/DDS1_SYNC_IN_P") (class "Default")
      (node (ref "IC9") (pin "32") (pinfunction "Q1_32") (pintype "output"))
    )
    (net (code "27") (name "/DDS2_SYNC_IN_N") (class "Default")
      (node (ref "IC9") (pin "25") (pinfunction "~{Q4}_25") (pintype "output"))
    )
    (net (code "28") (name "/DDS2_SYNC_IN_P") (class "Default")
      (node (ref "IC9") (pin "26") (pinfunction "Q4_26") (pintype "output"))
    )
    (net (code "29") (name "/DDS3_SYNC_IN_N") (class "Default")
      (node (ref "IC9") (pin "27") (pinfunction "~{Q3}_27") (pintype "output"))
    )
    (net (code "30") (name "/DDS3_SYNC_IN_P") (class "Default")
      (node (ref "IC9") (pin "28") (pinfunction "Q3_28") (pintype "output"))
    )
    (net (code "78") (name "/DDS_SYNC_CLK0") (class "Default")
      (node (ref "R31") (pin "2") (pinfunction "2_2") (pintype "passive"))
    )
    (net (code "79") (name "/DDS_SYNC_CLKSEL") (class "Default")
      (node (ref "R152") (pin "1") (pinfunction "1_1") (pintype "passive"))
    )
    (net (code "80") (name "/DDS_SYNC_CLK_OUTEN") (class "Default")
      (node (ref "IC4") (pin "3") (pinfunction "EN_3") (pintype "input"))
    )
    (net (code "81") (name "/DDS_SYNC_OUTEN") (class "Default")
      (node (ref "IC16") (pin "3") (pinfunction "EN_3") (pintype "input"))
      (node (ref "R153") (pin "1") (pinfunction "1_1") (pintype "passive"))
    )
    (net (code "103") (name "/FB_SYNC_N") (class "Default")
      (node (ref "IC16") (pin "1") (pinfunction "RIN-_1") (pintype "input"))
      (node (ref "IC9") (pin "20") (pinfunction "~{Q5}_20") (pintype "output"))
      (node (ref "R114") (pin "2") (pinfunction "2_2") (pintype "passive"))
    )
    (net (code "104") (name "/FB_SYNC_P") (class "Default")
      (node (ref "IC16") (pin "8") (pinfunction "RIN+_8") (pintype "input"))
      (node (ref "IC9") (pin "21") (pinfunction "Q5_21") (pintype "output"))
      (node (ref "R114") (pin "1") (pinfunction "1_1") (pintype "passive"))
    )
    (net (code "108") (name "/INT_CLK_IN") (class "Default")
      (node (ref "J7") (pin "1") (pinfunction "1_1") (pintype "bidirectional"))
    )
    (net (code "110") (name "/LED0") (class "Default")
      (node (ref "R27") (pin "1") (pinfunction "1_1") (pintype "passive"))
    )
    (net (code "111") (name "/LED1") (class "Default")
      (node (ref "R28") (pin "1") (pinfunction "1_1") (pintype "passive"))
    )
    (net (code "112") (name "/LED2") (class "Default")
      (node (ref "R29") (pin "1") (pinfunction "1_1") (pintype "passive"))
    )
    (net (code "113") (name "/LED3") (class "Default")
      (node (ref "R30") (pin "1") (pinfunction "1_1") (pintype "passive"))
    )
    (net (code "114") (name "/LED4") (class "Default")
      (node (ref "R43") (pin "1") (pinfunction "1_1") (pintype "passive"))
    )
    (net (code "115") (name "/LED5") (class "Default")
      (node (ref "R44") (pin "1") (pinfunction "1_1") (pintype "passive"))
    )
    (net (code "116") (name "/LED6") (class "Default")
      (node (ref "R25") (pin "1") (pinfunction "1_1") (pintype "passive"))
    )
    (net (code "117") (name "/LED7") (class "Default")
      (node (ref "R26") (pin "1") (pinfunction "1_1") (pintype "passive"))
    )
    (net (code "119") (name "/LVDS0_N") (class "Default")
      (node (ref "IC4") (pin "5") (pinfunction "DOUT-_5") (pintype "output"))
    )
    (net (code "121") (name "/LVDS0_P") (class "Default")
      (node (ref "IC4") (pin "6") (pinfunction "DOUT+_6") (pintype "output"))
    )
    (net (code "124") (name "/LVDS1_N_1") (class "Default")
      (node (ref "IC16") (pin "5") (pinfunction "DOUT-_5") (pintype "output"))
    )
    (net (code "126") (name "/LVDS1_P_1") (class "Default")
      (node (ref "IC16") (pin "6") (pinfunction "DOUT+_6") (pintype "output"))
    )
    (net (code "128") (name "/LVDS7_N_1") (class "Default")
      (node (ref "IC9") (pin "11") (pinfunction "~{CLK0}_11") (pintype "input"))
    )
    (net (code "130") (name "/LVDS7_P_1") (class "Default")
      (node (ref "IC9") (pin "10") (pinfunction "CLK0_10") (pintype "input"))
    )
    (net (code "136") (name "/RF_OUT0") (class "Default")
      (node (ref "J3") (pin "1") (pinfunction "1_1") (pintype "bidirectional"))
    )
    (net (code "137") (name "/RF_OUT1") (class "Default")
      (node (ref "J4") (pin "1") (pinfunction "1_1") (pintype "bidirectional"))
    )
    (net (code "138") (name "/RF_OUT2") (class "Default")
      (node (ref "J5") (pin "1") (pinfunction "1_1") (pintype "bidirectional"))
    )
    (net (code "139") (name "/RF_OUT3") (class "Default")
      (node (ref "J6") (pin "1") (pinfunction "1_1") (pintype "bidirectional"))
    )
    (net (code "142") (name "/SG0") (class "Default")
      (node (ref "C37") (pin "1") (pinfunction "1_1") (pintype "passive"))
      (node (ref "C42") (pin "2") (pinfunction "2_2") (pintype "passive"))
      (node (ref "J2") (pin "2") (pinfunction "2_2") (pintype "bidirectional"))
      (node (ref "R6") (pin "2") (pinfunction "2_2") (pintype "passive"))
    )
    (net (code "143") (name "/SG1") (class "Default")
      (node (ref "C11") (pin "1") (pinfunction "1_1") (pintype "passive"))
      (node (ref "C25") (pin "2") (pinfunction "2_2") (pintype "passive"))
      (node (ref "J3") (pin "2") (pinfunction "2_2") (pintype "bidirectional"))
      (node (ref "R64") (pin "2") (pinfunction "2_2") (pintype "passive"))
    )
    (net (code "144") (name "/SG2") (class "Default")
      (node (ref "C31") (pin "1") (pinfunction "1_1") (pintype "passive"))
      (node (ref "C32") (pin "2") (pinfunction "2_2") (pintype "passive"))
      (node (ref "J4") (pin "2") (pinfunction "2_2") (pintype "bidirectional"))
      (node (ref "R65") (pin "2") (pinfunction "2_2") (pintype "passive"))
    )
    (net (code "145") (name "/SG3") (class "Default")
      (node (ref "C33") (pin "1") (pinfunction "1_1") (pintype "passive"))
      (node (ref "C34") (pin "2") (pinfunction "2_2") (pintype "passive"))
      (node (ref "J5") (pin "2") (pinfunction "2_2") (pintype "bidirectional"))
      (node (ref "R74") (pin "2") (pinfunction "2_2") (pintype "passive"))
    )
    (net (code "146") (name "/SG4") (class "Default")
      (node (ref "C35") (pin "1") (pinfunction "1_1") (pintype "passive"))
      (node (ref "C41") (pin "2") (pinfunction "2_2") (pintype "passive"))
      (node (ref "J6") (pin "2") (pinfunction "2_2") (pintype "bidirectional"))
      (node (ref "R75") (pin "2") (pinfunction "2_2") (pintype "passive"))
    )
    (net (code "179") (name "GND") (class "Default")
      (node (ref "C1") (pin "1") (pinfunction "1_1") (pintype "passive"))
      (node (ref "C11") (pin "2") (pinfunction "2_2") (pintype "passive"))
      (node (ref "C13") (pin "1") (pinfunction "1_1") (pintype "passive"))
      (node (ref "C25") (pin "1") (pinfunction "1_1") (pintype "passive"))
      (node (ref "C31") (pin "2") (pinfunction "2_2") (pintype "passive"))
      (node (ref "C32") (pin "1") (pinfunction "1_1") (pintype "passive"))
      (node (ref "C33") (pin "2") (pinfunction "2_2") (pintype "passive"))
      (node (ref "C34") (pin "1") (pinfunction "1_1") (pintype "passive"))
      (node (ref "C35") (pin "2") (pinfunction "2_2") (pintype "passive"))
      (node (ref "C37") (pin "2") (pinfunction "2_2") (pintype "passive"))
      (node (ref "C41") (pin "1") (pinfunction "1_1") (pintype "passive"))
      (node (ref "C42") (pin "1") (pinfunction "1_1") (pintype "passive"))
      (node (ref "C45") (pin "1") (pinfunction "1_1") (pintype "passive"))
      (node (ref "C46") (pin "1") (pinfunction "1_1") (pintype "passive"))
      (node (ref "C86") (pin "1") (pinfunction "1_1") (pintype "passive"))
      (node (ref "C89") (pin "1") (pinfunction "1_1") (pintype "passive"))
      (node (ref "C90") (pin "1") (pinfunction "1_1") (pintype "passive"))
      (node (ref "CLIP1") (pin "1") (pinfunction "1_1") (pintype "passive"))
      (node (ref "CLIP10") (pin "1") (pinfunction "1_1") (pintype "passive"))
      (node (ref "CLIP11") (pin "1") (pinfunction "1_1") (pintype "passive"))
      (node (ref "CLIP12") (pin "1") (pinfunction "1_1") (pintype "passive"))
      (node (ref "CLIP13") (pin "1") (pinfunction "1_1") (pintype "passive"))
      (node (ref "CLIP14") (pin "1") (pinfunction "1_1") (pintype "passive"))
      (node (ref "CLIP15") (pin "1") (pinfunction "1_1") (pintype "passive"))
      (node (ref "CLIP16") (pin "1") (pinfunction "1_1") (pintype "passive"))
      (node (ref "CLIP17") (pin "1") (pinfunction "1_1") (pintype "passive"))
      (node (ref "CLIP18") (pin "1") (pinfunction "1_1") (pintype "passive"))
      (node (ref "CLIP19") (pin "1") (pinfunction "1_1") (pintype "passive"))
      (node (ref "CLIP2") (pin "1") (pinfunction "1_1") (pintype "passive"))
      (node (ref "CLIP20") (pin "1") (pinfunction "1_1") (pintype "passive"))
      (node (ref "CLIP21") (pin "1") (pinfunction "1_1") (pintype "passive"))
      (node (ref "CLIP22") (pin "1") (pinfunction "1_1") (pintype "passive"))
      (node (ref "CLIP23") (pin "1") (pinfunction "1_1") (pintype "passive"))
      (node (ref "CLIP24") (pin "1") (pinfunction "1_1") (pintype "passive"))
      (node (ref "CLIP25") (pin "1") (pinfunction "1_1") (pintype "passive"))
      (node (ref "CLIP26") (pin "1") (pinfunction "1_1") (pintype "passive"))
      (node (ref "CLIP27") (pin "1") (pinfunction "1_1") (pintype "passive"))
      (node (ref "CLIP28") (pin "1") (pinfunction "1_1") (pintype "passive"))
      (node (ref "CLIP29") (pin "1") (pinfunction "1_1") (pintype "passive"))
      (node (ref "CLIP3") (pin "1") (pinfunction "1_1") (pintype "passive"))
      (node (ref "CLIP30") (pin "1") (pinfunction "1_1") (pintype "passive"))
      (node (ref "CLIP31") (pin "1") (pinfunction "1_1") (pintype "passive"))
      (node (ref "CLIP4") (pin "1") (pinfunction "1_1") (pintype "passive"))
      (node (ref "CLIP5") (pin "1") (pinfunction "1_1") (pintype "passive"))
      (node (ref "CLIP6") (pin "1") (pinfunction "1_1") (pintype "passive"))
      (node (ref "CLIP7") (pin "1") (pinfunction "1_1") (pintype "passive"))
      (node (ref "CLIP8") (pin "1") (pinfunction "1_1") (pintype "passive"))
      (node (ref "CLIP9") (pin "1") (pinfunction "1_1") (pintype "passive"))
      (node (ref "IC16") (pin "2") (pinfunction "GND_2") (pintype "power_in"))
      (node (ref "IC16") (pin "4") (pinfunction "GND_4") (pintype "output"))
      (node (ref "IC4") (pin "2") (pinfunction "GND_2") (pintype "power_in"))
      (node (ref "IC4") (pin "4") (pinfunction "GND_4") (pintype "output"))
      (node (ref "IC9") (pin "12") (pinfunction "OE2_12") (pintype "input"))
      (node (ref "IC9") (pin "2") (pinfunction "SFOUTA1_2") (pintype "input"))
      (node (ref "IC9") (pin "22") (pinfunction "SFOUTB0_22") (pintype "input"))
      (node (ref "IC9") (pin "23") (pinfunction "SFOUTB1_23") (pintype "input"))
      (node (ref "IC9") (pin "3") (pinfunction "SFOUTA0_3") (pintype "input"))
      (node (ref "IC9") (pin "33") (pinfunction "GND_33") (pintype "power_in"))
      (node (ref "IC9") (pin "6") (pinfunction "GND_6") (pintype "power_in"))
      (node (ref "J7") (pin "2") (pinfunction "2_2") (pintype "bidirectional"))
      (node (ref "LD2") (pin "1") (pinfunction "C_1") (pintype "passive"))
      (node (ref "LD2") (pin "3") (pinfunction "C_3") (pintype "passive"))
      (node (ref "LD5") (pin "1") (pinfunction "C_1") (pintype "passive"))
      (node (ref "LD5") (pin "3") (pinfunction "C_3") (pintype "passive"))
      (node (ref "LD6") (pin "1") (pinfunction "C_1") (pintype "passive"))
      (node (ref "LD6") (pin "3") (pinfunction "C_3") (pintype "passive"))
      (node (ref "LD8") (pin "1") (pinfunction "C_1") (pintype "passive"))
      (node (ref "LD8") (pin "3") (pinfunction "C_3") (pintype "passive"))
      (node (ref "R39") (pin "1") (pinfunction "1_1") (pintype "passive"))
      (node (ref "R6") (pin "1") (pinfunction "1_1") (pintype "passive"))
      (node (ref "R64") (pin "1") (pinfunction "1_1") (pintype "passive"))
      (node (ref "R65") (pin "1") (pinfunction "1_1") (pintype "passive"))
      (node (ref "R74") (pin "1") (pinfunction "1_1") (pintype "passive"))
      (node (ref "R75") (pin "1") (pinfunction "1_1") (pintype "passive"))
    )
    (net (code "180") (name "Net-(IC4-RIN+)") (class "Default")
      (node (ref "IC4") (pin "8") (pinfunction "RIN+_8") (pintype "input"))
      (node (ref "R31") (pin "1") (pinfunction "1_1") (pintype "passive"))
      (node (ref "R32") (pin "2") (pinfunction "2_2") (pintype "passive"))
    )
    (net (code "181") (name "Net-(IC4-RIN-)") (class "Default")
      (node (ref "C1") (pin "2") (pinfunction "2_2") (pintype "passive"))
      (node (ref "IC4") (pin "1") (pinfunction "RIN-_1") (pintype "input"))
      (node (ref "R32") (pin "1") (pinfunction "1_1") (pintype "passive"))
      (node (ref "R36") (pin "1") (pinfunction "1_1") (pintype "passive"))
      (node (ref "R39") (pin "2") (pinfunction "2_2") (pintype "passive"))
    )
    (net (code "182") (name "Net-(IC9-CLK_SEL)") (class "Default")
      (node (ref "IC9") (pin "8") (pinfunction "CLK_SEL_8") (pintype "input"))
      (node (ref "R152") (pin "2") (pinfunction "2_2") (pintype "passive"))
    )
    (net (code "183") (name "Net-(IC9-OE5)") (class "Default")
      (node (ref "IC9") (pin "24") (pinfunction "OE5_24") (pintype "input"))
      (node (ref "R153") (pin "2") (pinfunction "2_2") (pintype "passive"))
    )
    (net (code "184") (name "Net-(LD2A-A)") (class "Default")
      (node (ref "LD2") (pin "2") (pinfunction "A_2") (pintype "passive"))
      (node (ref "R25") (pin "2") (pinfunction "2_2") (pintype "passive"))
    )
    (net (code "185") (name "Net-(LD2B-A)") (class "Default")
      (node (ref "LD2") (pin "4") (pinfunction "A_4") (pintype "passive"))
      (node (ref "R26") (pin "2") (pinfunction "2_2") (pintype "passive"))
    )
    (net (code "186") (name "Net-(LD5A-A)") (class "Default")
      (node (ref "LD5") (pin "2") (pinfunction "A_2") (pintype "passive"))
      (node (ref "R27") (pin "2") (pinfunction "2_2") (pintype "passive"))
    )
    (net (code "187") (name "Net-(LD5B-A)") (class "Default")
      (node (ref "LD5") (pin "4") (pinfunction "A_4") (pintype "passive"))
      (node (ref "R28") (pin "2") (pinfunction "2_2") (pintype "passive"))
    )
    (net (code "188") (name "Net-(LD6A-A)") (class "Default")
      (node (ref "LD6") (pin "2") (pinfunction "A_2") (pintype "passive"))
      (node (ref "R29") (pin "2") (pinfunction "2_2") (pintype "passive"))
    )
    (net (code "189") (name "Net-(LD6B-A)") (class "Default")
      (node (ref "LD6") (pin "4") (pinfunction "A_4") (pintype "passive"))
      (node (ref "R30") (pin "2") (pinfunction "2_2") (pintype "passive"))
    )
    (net (code "190") (name "Net-(LD8A-A)") (class "Default")
      (node (ref "LD8") (pin "2") (pinfunction "A_2") (pintype "passive"))
      (node (ref "R43") (pin "2") (pinfunction "2_2") (pintype "passive"))
    )
    (net (code "191") (name "Net-(LD8B-A)") (class "Default")
      (node (ref "LD8") (pin "4") (pinfunction "A_4") (pintype "passive"))
      (node (ref "R44") (pin "2") (pinfunction "2_2") (pintype "passive"))
    )
    (net (code "192") (name "P1V8A") (class "Default")
      (node (ref "R150") (pin "1") (pinfunction "1_1") (pintype "passive"))
    )
    (net (code "193") (name "P3V3") (class "Default")
      (node (ref "L13") (pin "2") (pinfunction "2_2") (pintype "passive"))
      (node (ref "L8") (pin "2") (pinfunction "2_2") (pintype "passive"))
    )
    (net (code "194") (name "P3V3_CLK1") (class "Default")
      (node (ref "C86") (pin "2") (pinfunction "2_2") (pintype "passive"))
      (node (ref "C89") (pin "2") (pinfunction "2_2") (pintype "passive"))
      (node (ref "C90") (pin "2") (pinfunction "2_2") (pintype "passive"))
      (node (ref "IC9") (pin "1") (pinfunction "OE0_1") (pintype "input"))
      (node (ref "IC9") (pin "13") (pinfunction "OE3_13") (pintype "input"))
      (node (ref "IC9") (pin "16") (pinfunction "OE4_16") (pintype "input"))
      (node (ref "IC9") (pin "18") (pinfunction "VDDOA_18") (pintype "power_in"))
      (node (ref "IC9") (pin "19") (pinfunction "VDDOB_19") (pintype "power_in"))
      (node (ref "IC9") (pin "7") (pinfunction "VDD_7") (pintype "power_in"))
      (node (ref "IC9") (pin "9") (pinfunction "OE1_9") (pintype "input"))
      (node (ref "L13") (pin "1") (pinfunction "1_1") (pintype "passive"))
      (node (ref "R150") (pin "2") (pinfunction "2_2") (pintype "passive"))
    )
    (net (code "195") (name "P3V3_CLK2") (class "Default")
      (node (ref "C13") (pin "2") (pinfunction "2_2") (pintype "passive"))
      (node (ref "C45") (pin "2") (pinfunction "2_2") (pintype "passive"))
      (node (ref "C46") (pin "2") (pinfunction "2_2") (pintype "passive"))
      (node (ref "IC16") (pin "7") (pinfunction "VCC_7") (pintype "power_in"))
      (node (ref "IC4") (pin "7") (pinfunction "VCC_7") (pintype "power_in"))
      (node (ref "L8") (pin "1") (pinfunction "1_1") (pintype "passive"))
      (node (ref "R36") (pin "2") (pinfunction "2_2") (pintype "passive"))
    )
    (net (code "196") (name "unconnected-(IC9-Q2-Pad30)") (class "Default")
      (node (ref "IC9") (pin "30") (pinfunction "Q2_30") (pintype "output"))
    )
    (net (code "197") (name "unconnected-(IC9-VREF-Pad17)") (class "Default")
      (node (ref "IC9") (pin "17") (pinfunction "VREF_17") (pintype "output"))
    )
    (net (code "198") (name "unconnected-(IC9-~{Q2}-Pad29)") (class "Default")
      (node (ref "IC9") (pin "29") (pinfunction "~{Q2}_29") (pintype "output"))
    )
  )
)
